# digital_IO.net
KiCad netlist of a schematic drawn in Altium Designer
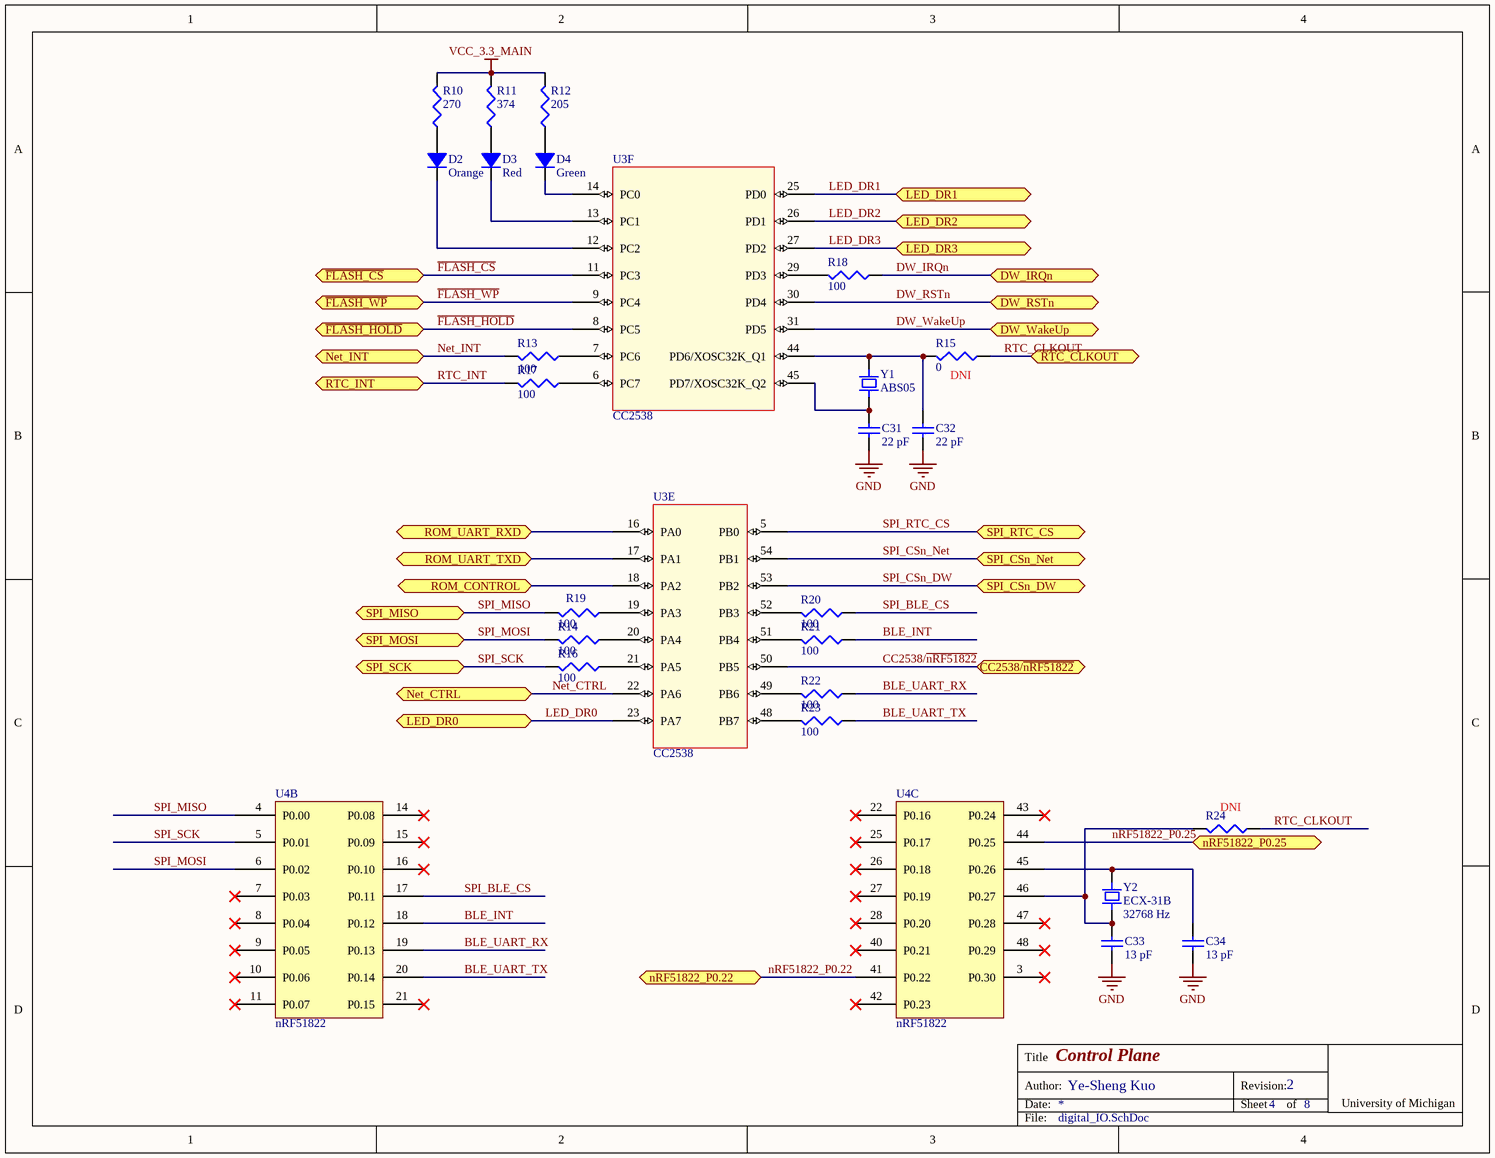
[diagram p0: digital_IO.SchDoc]

(export (version "E")
  (design (tool "Eeschema 10.0.6"))
  (components
    (comp (ref "C31")
      (value "22 pF")
      (footprint "0402")
      (description "Ceramic capacitor, 22 pF, 0402 package")
      (fields (field (name "TOLERANCE") "2%") (field (name "Comment") "Ceramic capacitor"))
      (libsource (lib "rlc") (part "C_22p_0402_ceramic"))
    )
    (comp (ref "C32")
      (value "22 pF")
      (footprint "0402")
      (description "Ceramic capacitor, 22 pF, 0402 package")
      (fields (field (name "TOLERANCE") "2%") (field (name "Comment") "Ceramic capacitor"))
      (libsource (lib "rlc") (part "C_22p_0402_ceramic"))
    )
    (comp (ref "C33")
      (value "13 pF")
      (footprint "0402")
      (description "Ceramic capacitor, 13 pF, 50 V, 0402 package")
      (fields (field (name "TOLERANCE") "5%") (field (name "Comment") "Ceramic capacitor"))
      (libsource (lib "rlc") (part "C_13p_0402_50V_ceramic"))
    )
    (comp (ref "C34")
      (value "13 pF")
      (footprint "0402")
      (description "Ceramic capacitor, 13 pF, 50 V, 0402 package")
      (fields (field (name "TOLERANCE") "5%") (field (name "Comment") "Ceramic capacitor"))
      (libsource (lib "rlc") (part "C_13p_0402_50V_ceramic"))
    )
    (comp (ref "D2")
      (value "LED, Orange")
      (footprint "0402 - DIODE")
      (description "LED, Orange, 0402")
      (fields (field (name "COLOR") "Orange"))
      (libsource (lib "rlc") (part "D_LED_ORANGE_0402"))
    )
    (comp (ref "D3")
      (value "LED, Red")
      (footprint "0402 - DIODE")
      (description "LED, Red, 0402")
      (fields (field (name "COLOR") "Red"))
      (libsource (lib "rlc") (part "D_LED_RED_0402"))
    )
    (comp (ref "D4")
      (value "LED, Green")
      (footprint "0402 - DIODE")
      (description "LED, Green,  0402")
      (fields (field (name "COLOR") "Green"))
      (libsource (lib "rlc") (part "D_LED_GREEN_0402"))
    )
    (comp (ref "R10")
      (value "270")
      (footprint "0402")
      (description "Chip resistor, 270, 0402 package")
      (fields (field (name "TOLERANCE") "1%") (field (name "POWER") "1/16 W"))
      (libsource (lib "rlc") (part "R_270_0402"))
    )
    (comp (ref "R11")
      (value "374")
      (footprint "0402")
      (description "Chip resistor, 374, 0402 package")
      (fields (field (name "TOLERANCE") "1%") (field (name "POWER") "1/16 W"))
      (libsource (lib "rlc") (part "R_374_0402"))
    )
    (comp (ref "R12")
      (value "205")
      (footprint "0402")
      (description "Chip resistor, 205, 0402 package")
      (fields (field (name "TOLERANCE") "1%") (field (name "POWER") "1/16 W"))
      (libsource (lib "rlc") (part "R_205_0402"))
    )
    (comp (ref "R13")
      (value "100")
      (footprint "0402")
      (description "Chip resistor, 100, 0402 package")
      (fields (field (name "TOLERANCE") "1%") (field (name "POWER") "1/16 W"))
      (libsource (lib "rlc") (part "R_100_0402"))
    )
    (comp (ref "R14")
      (value "100")
      (footprint "0402")
      (description "Chip resistor, 100, 0402 package")
      (fields (field (name "TOLERANCE") "1%") (field (name "POWER") "1/16 W"))
      (libsource (lib "rlc") (part "R_100_0402"))
    )
    (comp (ref "R15")
      (value "0")
      (footprint "0402")
      (description "Chip resistor, 0, 0402 package")
      (fields (field (name "Comment") "Chip resistor"))
      (libsource (lib "rlc") (part "R_0_0402"))
    )
    (comp (ref "R16")
      (value "100")
      (footprint "0402")
      (description "Chip resistor, 100, 0402 package")
      (fields (field (name "TOLERANCE") "1%") (field (name "POWER") "1/16 W"))
      (libsource (lib "rlc") (part "R_100_0402"))
    )
    (comp (ref "R17")
      (value "100")
      (footprint "0402")
      (description "Chip resistor, 100, 0402 package")
      (fields (field (name "TOLERANCE") "1%") (field (name "POWER") "1/16 W"))
      (libsource (lib "rlc") (part "R_100_0402"))
    )
    (comp (ref "R18")
      (value "100")
      (footprint "0402")
      (description "Chip resistor, 100, 0402 package")
      (fields (field (name "TOLERANCE") "1%") (field (name "POWER") "1/16 W"))
      (libsource (lib "rlc") (part "R_100_0402"))
    )
    (comp (ref "R19")
      (value "100")
      (footprint "0402")
      (description "Chip resistor, 100, 0402 package")
      (fields (field (name "TOLERANCE") "1%") (field (name "POWER") "1/16 W"))
      (libsource (lib "rlc") (part "R_100_0402"))
    )
    (comp (ref "R20")
      (value "100")
      (footprint "0402")
      (description "Chip resistor, 100, 0402 package")
      (fields (field (name "TOLERANCE") "1%") (field (name "POWER") "1/16 W"))
      (libsource (lib "rlc") (part "R_100_0402"))
    )
    (comp (ref "R21")
      (value "100")
      (footprint "0402")
      (description "Chip resistor, 100, 0402 package")
      (fields (field (name "TOLERANCE") "1%") (field (name "POWER") "1/16 W"))
      (libsource (lib "rlc") (part "R_100_0402"))
    )
    (comp (ref "R22")
      (value "100")
      (footprint "0402")
      (description "Chip resistor, 100, 0402 package")
      (fields (field (name "TOLERANCE") "1%") (field (name "POWER") "1/16 W"))
      (libsource (lib "rlc") (part "R_100_0402"))
    )
    (comp (ref "R23")
      (value "100")
      (footprint "0402")
      (description "Chip resistor, 100, 0402 package")
      (fields (field (name "TOLERANCE") "1%") (field (name "POWER") "1/16 W"))
      (libsource (lib "rlc") (part "R_100_0402"))
    )
    (comp (ref "R24")
      (value "0")
      (footprint "0402")
      (description "Chip resistor, 0, 0402 package")
      (fields (field (name "Comment") "Chip resistor"))
      (libsource (lib "rlc") (part "R_0_0402"))
    )
    (comp (ref "U3")
      (value "CC2538")
      (footprint "QFN56")
      (description "A Powerful System-On-Chip for 2.4-GHz IEEE 802.15.4, 6LoWPAN  and ZigBee Applications")
      (libsource (lib "sdl") (part "CC2538"))
    )
    (comp (ref "U4")
      (value "nRF51822")
      (footprint "QFN-48")
      (description "Multiprotocol Bluetooth® low energy/2.4 GHz RF System on Chip")
      (libsource (lib "sdl") (part "nRF51822"))
    )
    (comp (ref "Y1")
      (value "ABS05")
      (footprint "ABS05")
      (description "32768 Hz SMD Low profile crystal")
      (libsource (lib "crystal_oscillators_rtc") (part "ABS05"))
    )
    (comp (ref "Y2")
      (value "ECX-31B")
      (footprint "ECX-31B")
      (description "SMD TUNING FORK CRYSTAL")
      (fields (field (name "FREQUENCY") "32768 Hz"))
      (libsource (lib "crystal_oscillators_rtc") (part "ECX-31B"))
    )
  )
  (nets
    (net (code "1") (name "/BLE_INT") (class "Default")
      (node (ref "R21") (pin "2") (pintype "passive"))
      (node (ref "U4") (pin "18") (pinfunction "P0.12_18") (pintype "passive"))
    )
    (net (code "2") (name "/BLE_UART_RX") (class "Default")
      (node (ref "R22") (pin "2") (pintype "passive"))
      (node (ref "U4") (pin "19") (pinfunction "P0.13_19") (pintype "passive"))
    )
    (net (code "3") (name "/BLE_UART_TX") (class "Default")
      (node (ref "R23") (pin "2") (pintype "passive"))
      (node (ref "U4") (pin "20") (pinfunction "P0.14_20") (pintype "passive"))
    )
    (net (code "4") (name "/CC2538{slash}~{nRF51822}") (class "Default")
      (node (ref "U3") (pin "50") (pinfunction "PB5_50") (pintype "bidirectional"))
    )
    (net (code "5") (name "/DW_IRQn") (class "Default") (node (ref "R18") (pin "2") (pintype "passive")))
    (net (code "6") (name "/DW_RSTn") (class "Default")
      (node (ref "U3") (pin "30") (pinfunction "PD4_30") (pintype "bidirectional"))
    )
    (net (code "7") (name "/DW_WakeUp") (class "Default")
      (node (ref "U3") (pin "31") (pinfunction "PD5_31") (pintype "bidirectional"))
    )
    (net (code "8") (name "/LED_DR0") (class "Default")
      (node (ref "U3") (pin "23") (pinfunction "PA7_23") (pintype "bidirectional"))
    )
    (net (code "9") (name "/LED_DR1") (class "Default")
      (node (ref "U3") (pin "25") (pinfunction "PD0_25") (pintype "bidirectional"))
    )
    (net (code "10") (name "/LED_DR2") (class "Default")
      (node (ref "U3") (pin "26") (pinfunction "PD1_26") (pintype "bidirectional"))
    )
    (net (code "11") (name "/LED_DR3") (class "Default")
      (node (ref "U3") (pin "27") (pinfunction "PD2_27") (pintype "bidirectional"))
    )
    (net (code "12") (name "/Net_CTRL") (class "Default")
      (node (ref "U3") (pin "22") (pinfunction "PA6_22") (pintype "bidirectional"))
    )
    (net (code "13") (name "/Net_INT") (class "Default") (node (ref "R13") (pin "1") (pintype "passive")))
    (net (code "14") (name "/ROM_CONTROL") (class "Default")
      (node (ref "U3") (pin "18") (pinfunction "PA2_18") (pintype "bidirectional"))
    )
    (net (code "15") (name "/ROM_UART_RXD") (class "Default")
      (node (ref "U3") (pin "16") (pinfunction "PA0_16") (pintype "bidirectional"))
    )
    (net (code "16") (name "/ROM_UART_TXD") (class "Default")
      (node (ref "U3") (pin "17") (pinfunction "PA1_17") (pintype "bidirectional"))
    )
    (net (code "17") (name "/RTC_CLKOUT") (class "Default")
      (node (ref "R15") (pin "2") (pintype "passive"))
      (node (ref "R24") (pin "2") (pintype "passive"))
    )
    (net (code "18") (name "/RTC_INT") (class "Default") (node (ref "R17") (pin "1") (pintype "passive")))
    (net (code "19") (name "/SPI_BLE_CS") (class "Default")
      (node (ref "R20") (pin "2") (pintype "passive"))
      (node (ref "U4") (pin "17") (pinfunction "P0.11_17") (pintype "passive"))
    )
    (net (code "20") (name "/SPI_CSn_DW") (class "Default")
      (node (ref "U3") (pin "53") (pinfunction "PB2_53") (pintype "bidirectional"))
    )
    (net (code "21") (name "/SPI_CSn_Net") (class "Default")
      (node (ref "U3") (pin "54") (pinfunction "PB1_54") (pintype "bidirectional"))
    )
    (net (code "22") (name "/SPI_MISO") (class "Default")
      (node (ref "R19") (pin "1") (pintype "passive"))
      (node (ref "U4") (pin "4") (pinfunction "P0.00_4") (pintype "passive"))
    )
    (net (code "23") (name "/SPI_MOSI") (class "Default")
      (node (ref "R14") (pin "1") (pintype "passive"))
      (node (ref "U4") (pin "6") (pinfunction "P0.02_6") (pintype "passive"))
    )
    (net (code "24") (name "/SPI_RTC_CS") (class "Default")
      (node (ref "U3") (pin "5") (pinfunction "PB0_5") (pintype "bidirectional"))
    )
    (net (code "25") (name "/SPI_SCK") (class "Default")
      (node (ref "R16") (pin "1") (pintype "passive"))
      (node (ref "U4") (pin "5") (pinfunction "P0.01_5") (pintype "passive"))
    )
    (net (code "26") (name "/nRF51822_P0.22") (class "Default")
      (node (ref "U4") (pin "41") (pinfunction "P0.22_41") (pintype "passive"))
    )
    (net (code "27") (name "/nRF51822_P0.25") (class "Default")
      (node (ref "U4") (pin "44") (pinfunction "P0.25_44") (pintype "passive"))
    )
    (net (code "28") (name "/~{FLASH_CS}") (class "Default")
      (node (ref "U3") (pin "11") (pinfunction "PC3_11") (pintype "bidirectional"))
    )
    (net (code "29") (name "/~{FLASH_HOLD}") (class "Default")
      (node (ref "U3") (pin "8") (pinfunction "PC5_8") (pintype "bidirectional"))
    )
    (net (code "30") (name "/~{FLASH_WP}") (class "Default")
      (node (ref "U3") (pin "9") (pinfunction "PC4_9") (pintype "bidirectional"))
    )
    (net (code "31") (name "GND") (class "Default")
      (node (ref "C31") (pin "2") (pintype "passive"))
      (node (ref "C32") (pin "2") (pintype "passive"))
      (node (ref "C33") (pin "2") (pintype "passive"))
      (node (ref "C34") (pin "2") (pintype "passive"))
    )
    (net (code "32") (name "Net-(D2-Pad1)") (class "Default")
      (node (ref "D2") (pin "1") (pintype "passive"))
      (node (ref "R10") (pin "2") (pintype "passive"))
    )
    (net (code "33") (name "Net-(D3-Pad1)") (class "Default")
      (node (ref "D3") (pin "1") (pintype "passive"))
      (node (ref "R11") (pin "2") (pintype "passive"))
    )
    (net (code "34") (name "Net-(D4-Pad1)") (class "Default")
      (node (ref "D4") (pin "1") (pintype "passive"))
      (node (ref "R12") (pin "2") (pintype "passive"))
    )
    (net (code "35") (name "Net-(U3E-PA3)") (class "Default")
      (node (ref "R19") (pin "2") (pintype "passive"))
      (node (ref "U3") (pin "19") (pinfunction "PA3_19") (pintype "bidirectional"))
    )
    (net (code "36") (name "Net-(U3E-PA4)") (class "Default")
      (node (ref "R14") (pin "2") (pintype "passive"))
      (node (ref "U3") (pin "20") (pinfunction "PA4_20") (pintype "bidirectional"))
    )
    (net (code "37") (name "Net-(U3E-PA5)") (class "Default")
      (node (ref "R16") (pin "2") (pintype "passive"))
      (node (ref "U3") (pin "21") (pinfunction "PA5_21") (pintype "bidirectional"))
    )
    (net (code "38") (name "Net-(U3E-PB3)") (class "Default")
      (node (ref "R20") (pin "1") (pintype "passive"))
      (node (ref "U3") (pin "52") (pinfunction "PB3_52") (pintype "bidirectional"))
    )
    (net (code "39") (name "Net-(U3E-PB4)") (class "Default")
      (node (ref "R21") (pin "1") (pintype "passive"))
      (node (ref "U3") (pin "51") (pinfunction "PB4_51") (pintype "bidirectional"))
    )
    (net (code "40") (name "Net-(U3E-PB6)") (class "Default")
      (node (ref "R22") (pin "1") (pintype "passive"))
      (node (ref "U3") (pin "49") (pinfunction "PB6_49") (pintype "bidirectional"))
    )
    (net (code "41") (name "Net-(U3E-PB7)") (class "Default")
      (node (ref "R23") (pin "1") (pintype "passive"))
      (node (ref "U3") (pin "48") (pinfunction "PB7_48") (pintype "bidirectional"))
    )
    (net (code "42") (name "Net-(U3F-PC0)") (class "Default")
      (node (ref "D4") (pin "2") (pintype "passive"))
      (node (ref "U3") (pin "14") (pinfunction "PC0_14") (pintype "bidirectional"))
    )
    (net (code "43") (name "Net-(U3F-PC1)") (class "Default")
      (node (ref "D3") (pin "2") (pintype "passive"))
      (node (ref "U3") (pin "13") (pinfunction "PC1_13") (pintype "bidirectional"))
    )
    (net (code "44") (name "Net-(U3F-PC2)") (class "Default")
      (node (ref "D2") (pin "2") (pintype "passive"))
      (node (ref "U3") (pin "12") (pinfunction "PC2_12") (pintype "bidirectional"))
    )
    (net (code "45") (name "Net-(U3F-PC6)") (class "Default")
      (node (ref "R13") (pin "2") (pintype "passive"))
      (node (ref "U3") (pin "7") (pinfunction "PC6_7") (pintype "bidirectional"))
    )
    (net (code "46") (name "Net-(U3F-PC7)") (class "Default")
      (node (ref "R17") (pin "2") (pintype "passive"))
      (node (ref "U3") (pin "6") (pinfunction "PC7_6") (pintype "bidirectional"))
    )
    (net (code "47") (name "Net-(U3F-PD3)") (class "Default")
      (node (ref "R18") (pin "1") (pintype "passive"))
      (node (ref "U3") (pin "29") (pinfunction "PD3_29") (pintype "bidirectional"))
    )
    (net (code "48") (name "Net-(U3F-PD6{slash}XOSC32K_Q1)") (class "Default")
      (node (ref "C32") (pin "1") (pintype "passive"))
      (node (ref "R15") (pin "1") (pintype "passive"))
      (node (ref "U3") (pin "44") (pinfunction "PD6/XOSC32K_Q1_44") (pintype "bidirectional"))
      (node (ref "Y1") (pin "1") (pintype "passive"))
    )
    (net (code "49") (name "Net-(U3F-PD7{slash}XOSC32K_Q2)") (class "Default")
      (node (ref "C31") (pin "1") (pintype "passive"))
      (node (ref "U3") (pin "45") (pinfunction "PD7/XOSC32K_Q2_45") (pintype "bidirectional"))
      (node (ref "Y1") (pin "2") (pintype "passive"))
    )
    (net (code "50") (name "Net-(U4C-P0.26)") (class "Default")
      (node (ref "C34") (pin "1") (pintype "passive"))
      (node (ref "U4") (pin "45") (pinfunction "P0.26_45") (pintype "passive"))
      (node (ref "Y2") (pin "1") (pintype "passive"))
    )
    (net (code "51") (name "Net-(U4C-P0.27)") (class "Default")
      (node (ref "C33") (pin "1") (pintype "passive"))
      (node (ref "R24") (pin "1") (pintype "passive"))
      (node (ref "U4") (pin "46") (pinfunction "P0.27_46") (pintype "passive"))
      (node (ref "Y2") (pin "2") (pintype "passive"))
    )
    (net (code "52") (name "VCC_3.3_MAIN") (class "Default")
      (node (ref "R10") (pin "1") (pintype "passive"))
      (node (ref "R11") (pin "1") (pintype "passive"))
      (node (ref "R12") (pin "1") (pintype "passive"))
    )
    (net (code "53") (name "unconnected-(U4B-P0.03-Pad7)") (class "Default")
      (node (ref "U4") (pin "7") (pinfunction "P0.03_7") (pintype "passive+no_connect"))
    )
    (net (code "54") (name "unconnected-(U4B-P0.04-Pad8)") (class "Default")
      (node (ref "U4") (pin "8") (pinfunction "P0.04_8") (pintype "passive+no_connect"))
    )
    (net (code "55") (name "unconnected-(U4B-P0.05-Pad9)") (class "Default")
      (node (ref "U4") (pin "9") (pinfunction "P0.05_9") (pintype "passive+no_connect"))
    )
    (net (code "56") (name "unconnected-(U4B-P0.06-Pad10)") (class "Default")
      (node (ref "U4") (pin "10") (pinfunction "P0.06_10") (pintype "passive+no_connect"))
    )
    (net (code "57") (name "unconnected-(U4B-P0.07-Pad11)") (class "Default")
      (node (ref "U4") (pin "11") (pinfunction "P0.07_11") (pintype "passive+no_connect"))
    )
    (net (code "58") (name "unconnected-(U4B-P0.08-Pad14)") (class "Default")
      (node (ref "U4") (pin "14") (pinfunction "P0.08_14") (pintype "passive+no_connect"))
    )
    (net (code "59") (name "unconnected-(U4B-P0.09-Pad15)") (class "Default")
      (node (ref "U4") (pin "15") (pinfunction "P0.09_15") (pintype "passive+no_connect"))
    )
    (net (code "60") (name "unconnected-(U4B-P0.10-Pad16)") (class "Default")
      (node (ref "U4") (pin "16") (pinfunction "P0.10_16") (pintype "passive+no_connect"))
    )
    (net (code "61") (name "unconnected-(U4B-P0.15-Pad21)") (class "Default")
      (node (ref "U4") (pin "21") (pinfunction "P0.15_21") (pintype "passive+no_connect"))
    )
    (net (code "62") (name "unconnected-(U4C-P0.16-Pad22)") (class "Default")
      (node (ref "U4") (pin "22") (pinfunction "P0.16_22") (pintype "passive+no_connect"))
    )
    (net (code "63") (name "unconnected-(U4C-P0.17-Pad25)") (class "Default")
      (node (ref "U4") (pin "25") (pinfunction "P0.17_25") (pintype "passive+no_connect"))
    )
    (net (code "64") (name "unconnected-(U4C-P0.18-Pad26)") (class "Default")
      (node (ref "U4") (pin "26") (pinfunction "P0.18_26") (pintype "passive+no_connect"))
    )
    (net (code "65") (name "unconnected-(U4C-P0.19-Pad27)") (class "Default")
      (node (ref "U4") (pin "27") (pinfunction "P0.19_27") (pintype "passive+no_connect"))
    )
    (net (code "66") (name "unconnected-(U4C-P0.20-Pad28)") (class "Default")
      (node (ref "U4") (pin "28") (pinfunction "P0.20_28") (pintype "passive+no_connect"))
    )
    (net (code "67") (name "unconnected-(U4C-P0.21-Pad40)") (class "Default")
      (node (ref "U4") (pin "40") (pinfunction "P0.21_40") (pintype "passive+no_connect"))
    )
    (net (code "68") (name "unconnected-(U4C-P0.23-Pad42)") (class "Default")
      (node (ref "U4") (pin "42") (pinfunction "P0.23_42") (pintype "passive+no_connect"))
    )
    (net (code "69") (name "unconnected-(U4C-P0.24-Pad43)") (class "Default")
      (node (ref "U4") (pin "43") (pinfunction "P0.24_43") (pintype "passive+no_connect"))
    )
    (net (code "70") (name "unconnected-(U4C-P0.28-Pad47)") (class "Default")
      (node (ref "U4") (pin "47") (pinfunction "P0.28_47") (pintype "passive+no_connect"))
    )
    (net (code "71") (name "unconnected-(U4C-P0.29-Pad48)") (class "Default")
      (node (ref "U4") (pin "48") (pinfunction "P0.29_48") (pintype "passive+no_connect"))
    )
    (net (code "72") (name "unconnected-(U4C-P0.30-Pad3)") (class "Default")
      (node (ref "U4") (pin "3") (pinfunction "P0.30_3") (pintype "passive+no_connect"))
    )
  )
)
